# surfacemount.net
KiCad netlist of a schematic drawn in EAGLE
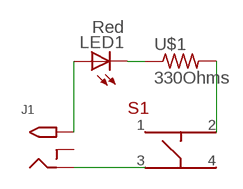
[diagram p0: schematic, sheet 1]

(export (version "E")
  (design (tool "Eeschema 10.0.6"))
  (components
    (comp (ref "J1")
      (value "2.1MMJACKTHM")
      (footprint "eagle-import:PJ-102A")
      (libsource (lib "eagle-import") (part "2.1MMJACKTHM"))
    )
    (comp (ref "LED1")
      (value "Red")
      (footprint "eagle-import:LED5MM")
      (libsource (lib "eagle-import") (part "LED5MM"))
    )
    (comp (ref "S1")
      (value "1301.9315")
      (footprint "eagle-import:1301.9315")
      (libsource (lib "eagle-import") (part "1301.9315"))
    )
    (comp (ref "U$1")
      (value "330Ohms")
      (footprint "eagle-import:RESAD1160W55L680D260_HS")
      (libsource (lib "eagle-import") (part "RESISTORTH-1/4W-CARBON"))
    )
  )
  (nets
    (net (code "1") (name "Net-(J1-PadRING)") (class "Default")
      (node (ref "J1") (pin "RING") (pinfunction "RING_RING") (pintype "bidirectional"))
      (node (ref "S1") (pin "3") (pinfunction "3_3") (pintype "bidirectional"))
    )
    (net (code "2") (name "Net-(J1-PadTIP)") (class "Default")
      (node (ref "J1") (pin "TIP") (pinfunction "TIP_TIP") (pintype "bidirectional"))
      (node (ref "LED1") (pin "A") (pinfunction "A_A") (pintype "passive"))
    )
    (net (code "3") (name "Net-(LED1-C)") (class "Default")
      (node (ref "LED1") (pin "K") (pinfunction "C_K") (pintype "passive"))
      (node (ref "U$1") (pin "1") (pinfunction "1_1") (pintype "passive"))
    )
    (net (code "4") (name "Net-(S1-Pad2)") (class "Default")
      (node (ref "S1") (pin "2") (pinfunction "2_2") (pintype "bidirectional"))
      (node (ref "U$1") (pin "2") (pinfunction "2_2") (pintype "passive"))
    )
    (net (code "5") (name "unconnected-(J1-PadRING_SW)") (class "Default")
      (node (ref "J1") (pin "RING_SW") (pinfunction "RING_SW_RING_SW") (pintype "bidirectional"))
    )
    (net (code "6") (name "unconnected-(S1-Pad1)") (class "Default")
      (node (ref "S1") (pin "1") (pinfunction "1_1") (pintype "bidirectional"))
    )
    (net (code "7") (name "unconnected-(S1-Pad4)") (class "Default")
      (node (ref "S1") (pin "4") (pinfunction "4_4") (pintype "bidirectional"))
    )
  )
)
